# Photoelectric_tube_to_Ammeter.net
KiCad netlist of a schematic drawn in Altium Designer
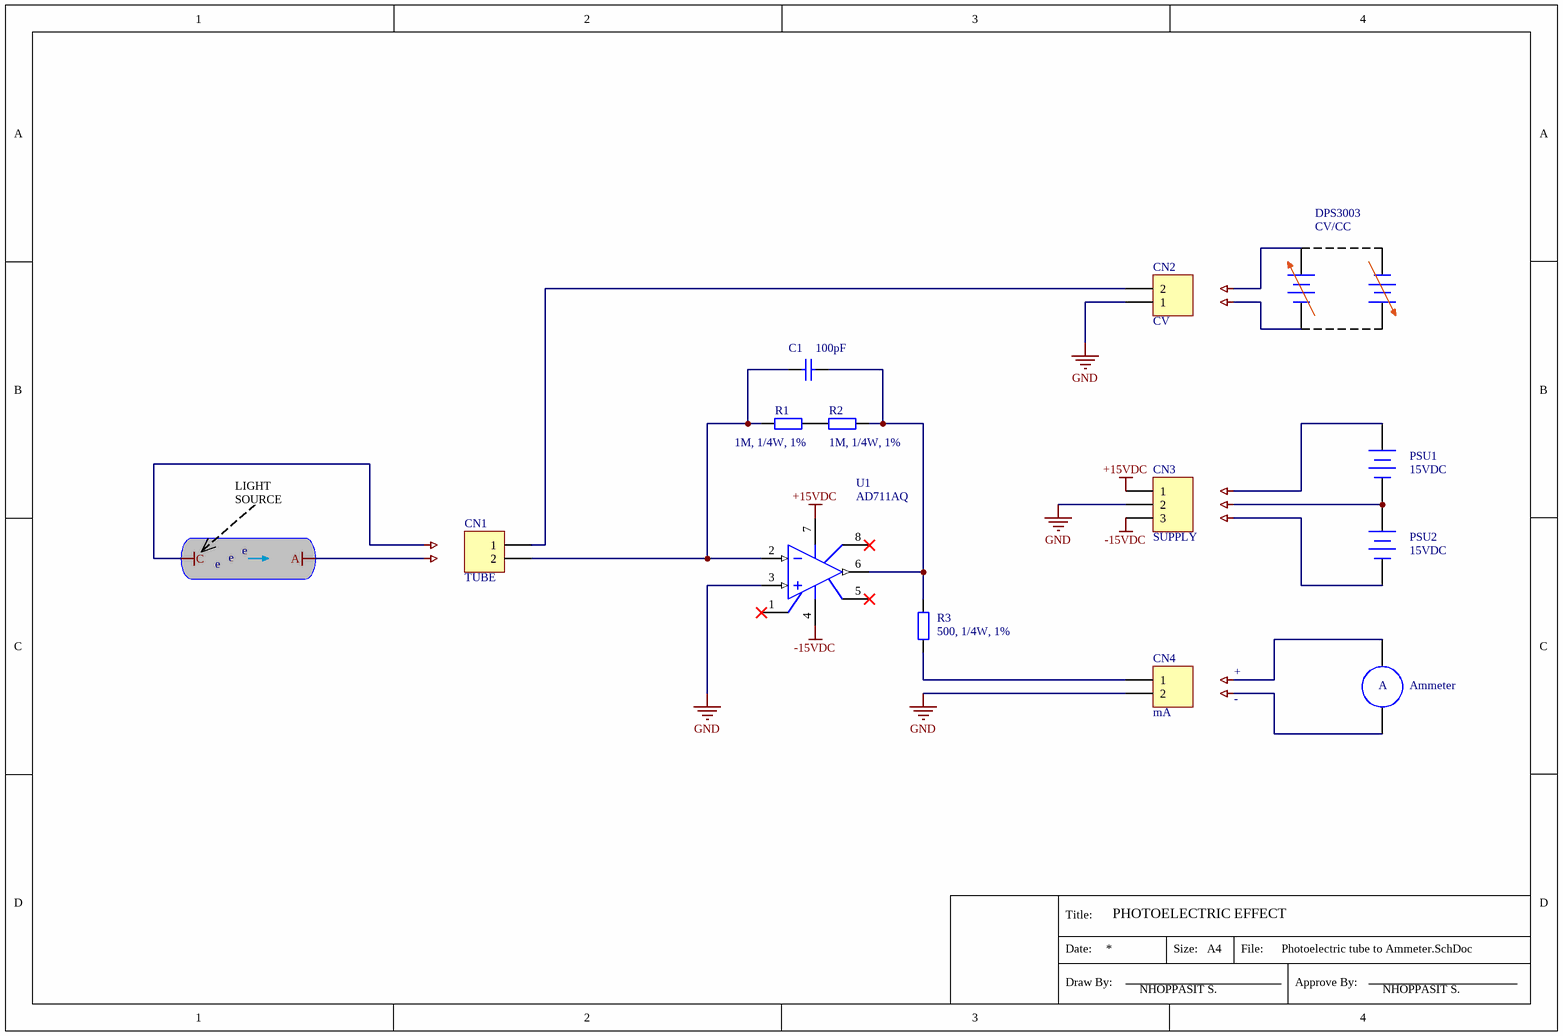
[diagram p0: Photoelectric tube to Ammeter.SchDoc]

(export (version "E")
  (design (tool "Eeschema 10.0.6"))
  (components
    (comp (ref "Ammeter")
      (value "A")
      (description "Indicating Instrument")
      (fields (field (name "PUBLISHER") "Altium Limited"))
      (libsource (lib "Miscellaneous Devices") (part "Meter"))
    )
    (comp (ref "C1")
      (value "100pF")
      (footprint "C.2")
      (description "Capacitor")
      (fields (field (name "PUBLISHER") "Altium Limited"))
      (libsource (lib "Miscellaneous Devices") (part "Cap"))
    )
    (comp (ref "CN1")
      (value "TUBE")
      (footprint "DG126-5.0 2P")
      (description "Header, 2-Pin, Right Angle")
      (fields (field (name "PUBLISHER") "Altium Limited"))
      (libsource (lib "") (part "Header 2H_2"))
    )
    (comp (ref "CN2")
      (value "CV")
      (footprint "DG126-5.0 2P")
      (description "Header, 2-Pin, Right Angle")
      (fields (field (name "PUBLISHER") "Altium Limited"))
      (libsource (lib "Miscellaneous Connectors") (part "Header 2H"))
    )
    (comp (ref "CN3")
      (value "SUPPLY")
      (footprint "DG126-5.0 3P")
      (description "Header, 3-Pin, Right Angle")
      (fields (field (name "PUBLISHER") "Altium Limited"))
      (libsource (lib "Miscellaneous Connectors") (part "Header 3H"))
    )
    (comp (ref "CN4")
      (value "mA")
      (footprint "DG126-5.0 2P")
      (description "Header, 2-Pin, Right Angle")
      (fields (field (name "PUBLISHER") "Altium Limited"))
      (libsource (lib "") (part "Header 2H_1"))
    )
    (comp (ref "CV/CC")
      (value "DPS3003")
      (description "Multicell Battery")
      (fields (field (name "PUBLISHER") "Altium Limited"))
      (libsource (lib "Miscellaneous Devices") (part "Battery"))
    )
    (comp (ref "PSU0")
      (value "15VDC")
      (description "Multicell Battery")
      (fields (field (name "PUBLISHER") "Altium Limited"))
      (libsource (lib "Miscellaneous Devices") (part "Battery"))
    )
    (comp (ref "PSU1")
      (value "15VDC")
      (description "Multicell Battery")
      (fields (field (name "PUBLISHER") "Altium Limited"))
      (libsource (lib "Miscellaneous Devices") (part "Battery"))
    )
    (comp (ref "PSU2")
      (value "15VDC")
      (description "Multicell Battery")
      (fields (field (name "PUBLISHER") "Altium Limited"))
      (libsource (lib "Miscellaneous Devices") (part "Battery"))
    )
    (comp (ref "R1")
      (value "1M, 1/4W, 1%")
      (footprint "AXIAL-0.4")
      (description "Resistor")
      (fields (field (name "PUBLISHER") "Altium Limited"))
      (libsource (lib "") (part "Res2_1"))
    )
    (comp (ref "R2")
      (value "1M, 1/4W, 1%")
      (footprint "AXIAL-0.4")
      (description "Resistor")
      (fields (field (name "PUBLISHER") "Altium Limited"))
      (libsource (lib "") (part "Res2_1"))
    )
    (comp (ref "R3")
      (value "500, 1/4W, 1%")
      (footprint "AXIAL-0.4")
      (description "Resistor")
      (fields (field (name "PUBLISHER") "Altium Limited"))
      (libsource (lib "Miscellaneous Devices") (part "Res2"))
    )
    (comp (ref "U1")
      (value "AD711AQ")
      (footprint "DIP-8")
      (description "Precision Low Cost High-Speed BiFET Operational Amplifier")
      (fields (field (name "PUBLISHER") "Altium Limited"))
      (libsource (lib "AD Operational Amplifier") (part "AD711AQ"))
    )
  )
  (nets
    (net (code "1") (name "+15VDC") (class "Default")
      (node (ref "CN3") (pin "1") (pinfunction "1_1") (pintype "passive"))
      (node (ref "U1") (pin "7") (pinfunction "V+_7") (pintype "power_in"))
    )
    (net (code "2") (name "-15VDC") (class "Default")
      (node (ref "CN3") (pin "3") (pinfunction "3_3") (pintype "passive"))
      (node (ref "U1") (pin "4") (pinfunction "V-_4") (pintype "power_in"))
    )
    (net (code "3") (name "A") (class "Default")
      (node (ref "Ammeter") (pin "1") (pinfunction "1_1") (pintype "passive"))
      (node (ref "Ammeter") (pin "2") (pinfunction "2_2") (pintype "passive"))
      (node (ref "CV/CC") (pin "1") (pinfunction "+_1") (pintype "passive"))
      (node (ref "CV/CC") (pin "2") (pinfunction "-_2") (pintype "passive"))
      (node (ref "PSU1") (pin "1") (pinfunction "+_1") (pintype "passive"))
      (node (ref "PSU1") (pin "2") (pinfunction "-_2") (pintype "passive"))
      (node (ref "PSU2") (pin "1") (pinfunction "+_1") (pintype "passive"))
      (node (ref "PSU2") (pin "2") (pinfunction "-_2") (pintype "passive"))
    )
    (net (code "4") (name "GND") (class "Default")
      (node (ref "CN2") (pin "1") (pinfunction "1_1") (pintype "passive"))
      (node (ref "CN3") (pin "2") (pinfunction "2_2") (pintype "passive"))
      (node (ref "CN4") (pin "2") (pinfunction "2_2") (pintype "passive"))
      (node (ref "U1") (pin "3") (pinfunction "IN+_3") (pintype "input"))
    )
    (net (code "5") (name "Net-(CN1-Pad1)") (class "Default")
      (node (ref "CN1") (pin "1") (pinfunction "1_1") (pintype "passive"))
      (node (ref "CN2") (pin "2") (pinfunction "2_2") (pintype "passive"))
    )
    (net (code "6") (name "Net-(CN4-Pad1)") (class "Default")
      (node (ref "CN4") (pin "1") (pinfunction "1_1") (pintype "passive"))
      (node (ref "R3") (pin "1") (pinfunction "1_1") (pintype "passive"))
    )
    (net (code "7") (name "Net-(R1-Pad2)") (class "Default")
      (node (ref "R1") (pin "2") (pinfunction "2_2") (pintype "passive"))
      (node (ref "R2") (pin "1") (pinfunction "1_1") (pintype "passive"))
    )
    (net (code "8") (name "Net-(U1-IN-)") (class "Default")
      (node (ref "C1") (pin "1") (pinfunction "1_1") (pintype "passive"))
      (node (ref "CN1") (pin "2") (pinfunction "2_2") (pintype "passive"))
      (node (ref "R1") (pin "1") (pinfunction "1_1") (pintype "passive"))
      (node (ref "U1") (pin "2") (pinfunction "IN-_2") (pintype "input"))
    )
    (net (code "9") (name "Net-(U1-OUT)") (class "Default")
      (node (ref "C1") (pin "2") (pinfunction "2_2") (pintype "passive"))
      (node (ref "R2") (pin "2") (pinfunction "2_2") (pintype "passive"))
      (node (ref "R3") (pin "2") (pinfunction "2_2") (pintype "passive"))
      (node (ref "U1") (pin "6") (pinfunction "OUT_6") (pintype "output"))
    )
    (net (code "10") (name "unconnected-(PSU0-+-Pad1)") (class "Default")
      (node (ref "PSU0") (pin "1") (pinfunction "+_1") (pintype "passive"))
    )
    (net (code "11") (name "unconnected-(PSU0---Pad2)") (class "Default")
      (node (ref "PSU0") (pin "2") (pinfunction "-_2") (pintype "passive"))
    )
    (net (code "12") (name "unconnected-(U1-NC-Pad8)") (class "Default")
      (node (ref "U1") (pin "8") (pinfunction "NC_8") (pintype "passive+no_connect"))
    )
    (net (code "13") (name "unconnected-(U1-OS_NULL-Pad1)") (class "Default")
      (node (ref "U1") (pin "1") (pinfunction "OS_NULL_1") (pintype "passive+no_connect"))
    )
    (net (code "14") (name "unconnected-(U1-OS_NULL-Pad5)") (class "Default")
      (node (ref "U1") (pin "5") (pinfunction "OS_NULL_5") (pintype "passive+no_connect"))
    )
  )
)
